# ShuntAmp.net
KiCad netlist of a schematic drawn in Altium Designer
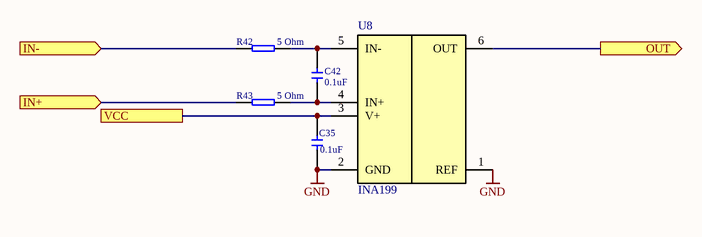
[diagram p0: ShuntAmp.SchDoc]

(export (version "E")
  (design (tool "Eeschema 10.0.6"))
  (components
    (comp (ref "C35")
      (value "0.1uF")
      (footprint "CERCAP 0402")
      (description "Capacitor")
      (fields (field (name "VOLTAGE") "50V") (field (name "Comment") "CERCAP 0402 0.1uF 50V X7R"))
      (libsource (lib "!main") (part "!Capacitor"))
    )
    (comp (ref "C42")
      (value "0.1uF")
      (footprint "CERCAP 0402")
      (description "Capacitor")
      (fields (field (name "VOLTAGE") "50V") (field (name "Comment") "CERCAP 0402 0.1uF 50V X7R"))
      (libsource (lib "!main") (part "!Capacitor"))
    )
    (comp (ref "R42")
      (value "5 Ohm")
      (footprint "RES 0402")
      (description "Resistor")
      (fields (field (name "Comment") "RES 0402 5 Ohm"))
      (libsource (lib "!main") (part "!Resistor"))
    )
    (comp (ref "R43")
      (value "5 Ohm")
      (footprint "RES 0402")
      (description "Resistor")
      (fields (field (name "Comment") "RES 0402 5 Ohm"))
      (libsource (lib "!main") (part "!Resistor"))
    )
    (comp (ref "U8")
      (value "INA199")
      (footprint "SOT-323-6 (SC-70)")
      (description "Current shunt monitor")
      (libsource (lib "analog") (part "INA199"))
    )
  )
  (nets
    (net (code "1") (name "/IN+") (class "Default")
      (node (ref "R43") (pin "1") (pinfunction "11_1") (pintype "passive"))
    )
    (net (code "2") (name "/IN-") (class "Default")
      (node (ref "R42") (pin "1") (pinfunction "11_1") (pintype "passive"))
    )
    (net (code "3") (name "/OUT") (class "Default")
      (node (ref "U8") (pin "6") (pinfunction "OUT_6") (pintype "passive"))
    )
    (net (code "4") (name "/VCC") (class "Default")
      (node (ref "C35") (pin "2") (pintype "passive"))
      (node (ref "U8") (pin "3") (pinfunction "V+_3") (pintype "passive"))
    )
    (net (code "5") (name "GND") (class "Default")
      (node (ref "C35") (pin "1") (pintype "passive"))
      (node (ref "U8") (pin "1") (pinfunction "REF_1") (pintype "passive"))
      (node (ref "U8") (pin "2") (pinfunction "GND_2") (pintype "passive"))
    )
    (net (code "6") (name "Net-(R42-12)") (class "Default")
      (node (ref "C42") (pin "2") (pintype "passive"))
      (node (ref "R42") (pin "2") (pinfunction "12_2") (pintype "passive"))
      (node (ref "U8") (pin "5") (pinfunction "IN-_5") (pintype "passive"))
    )
    (net (code "7") (name "Net-(R43-12)") (class "Default")
      (node (ref "C42") (pin "1") (pintype "passive"))
      (node (ref "R43") (pin "2") (pinfunction "12_2") (pintype "passive"))
      (node (ref "U8") (pin "4") (pinfunction "IN+_4") (pintype "passive"))
    )
  )
)
